# VFD_Board.net
KiCad netlist of a schematic drawn in EAGLE
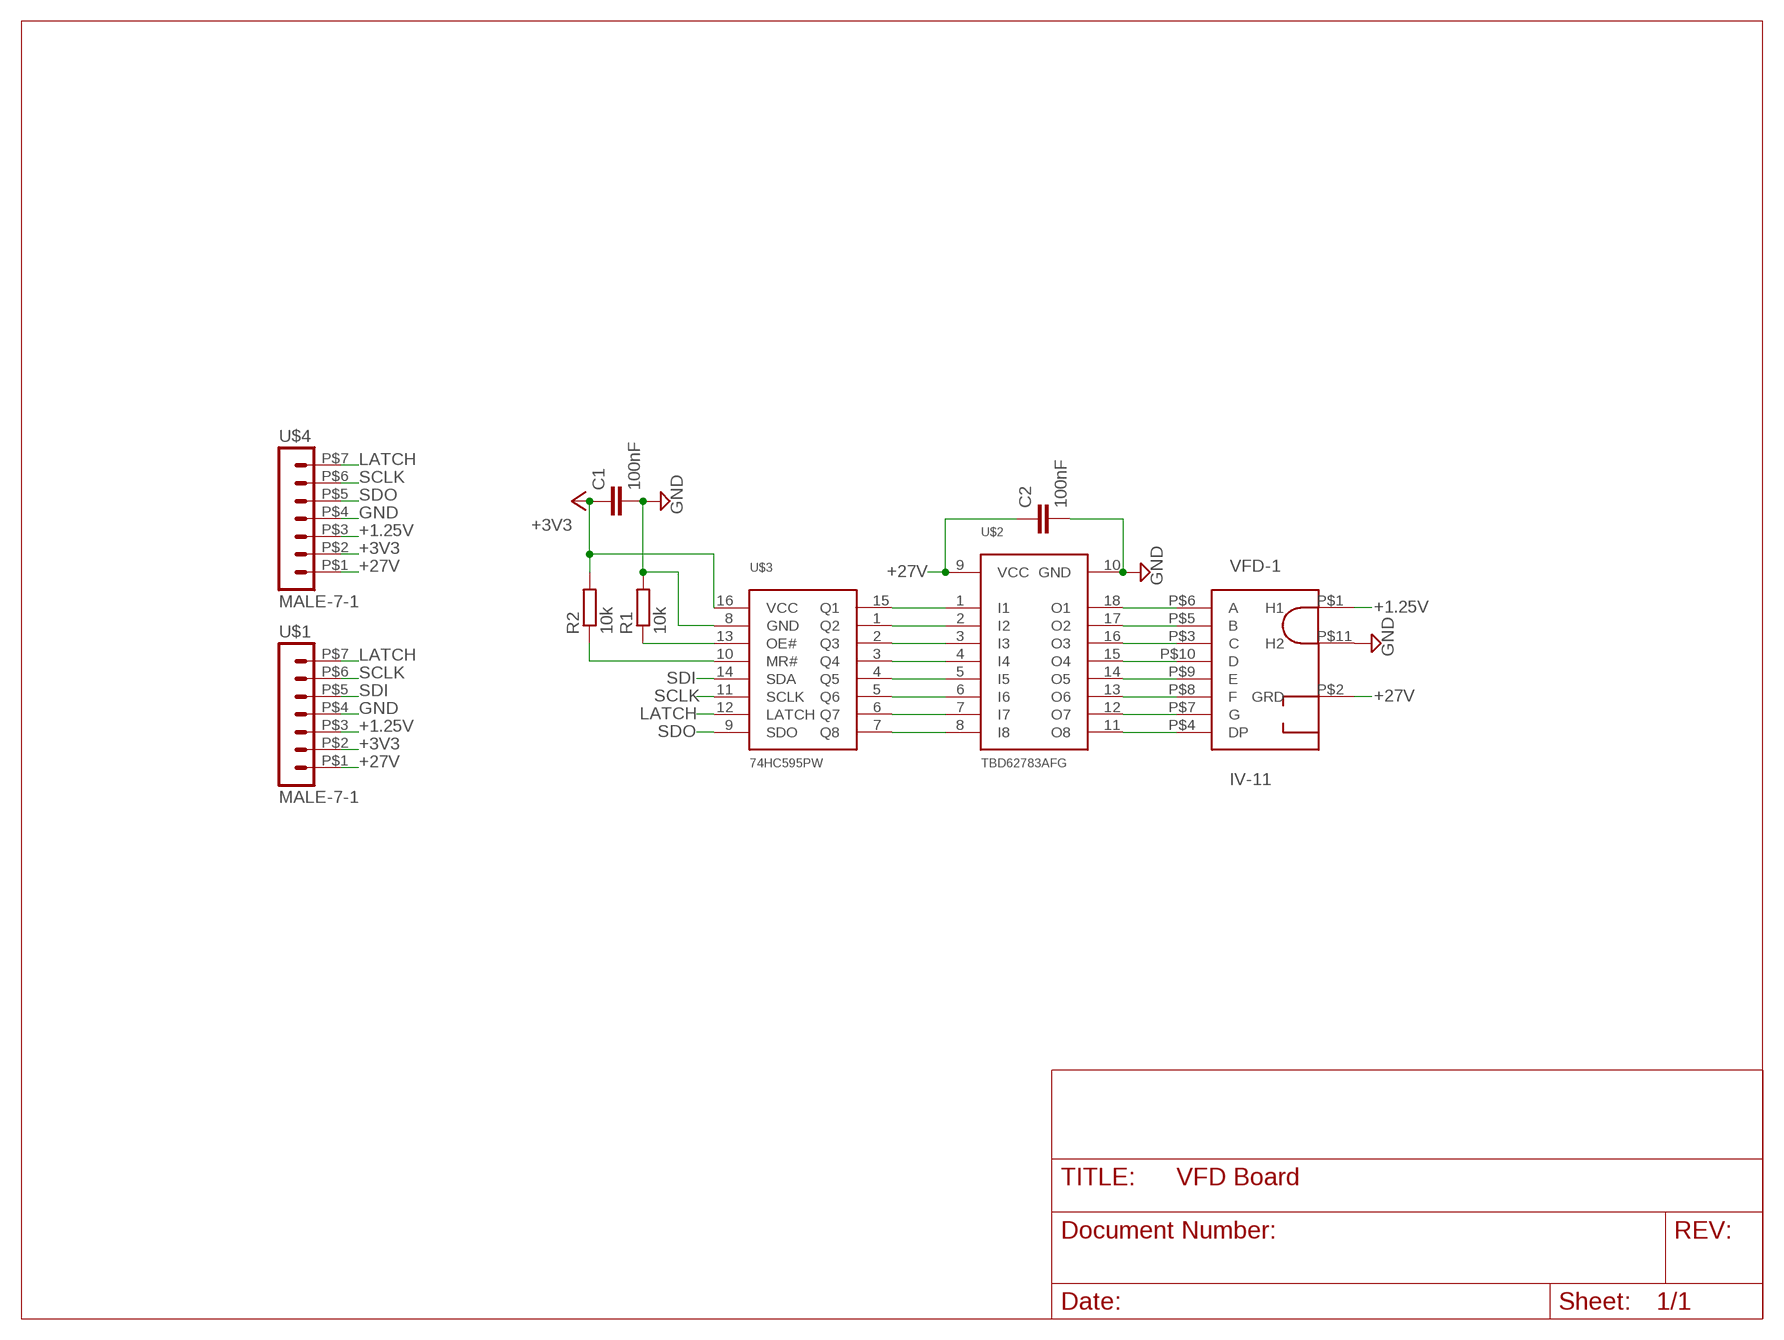
[diagram p0: schematic, sheet 1]

(export (version "E")
  (design (tool "Eeschema 10.0.6"))
  (components
    (comp (ref "C1")
      (value "100nF")
      (footprint "eagle-import:C0603")
      (libsource (lib "eagle-import") (part "C-EUC0603"))
    )
    (comp (ref "C2")
      (value "100nF")
      (footprint "eagle-import:C0603")
      (libsource (lib "eagle-import") (part "C-EUC0603"))
    )
    (comp (ref "R1")
      (value "10k")
      (footprint "eagle-import:R0603")
      (libsource (lib "eagle-import") (part "R-EU_R0603"))
    )
    (comp (ref "R2")
      (value "10k")
      (footprint "eagle-import:R0603")
      (libsource (lib "eagle-import") (part "R-EU_R0603"))
    )
    (comp (ref "U$1")
      (value "MALE-7-1")
      (footprint "eagle-import:7-PIN-HEADER")
      (libsource (lib "eagle-import") (part "MALE-7-1"))
    )
    (comp (ref "U$2")
      (value "TBD62783AFG")
      (footprint "eagle-import:SOIC18L")
      (libsource (lib "eagle-import") (part "TBD62783AFG"))
    )
    (comp (ref "U$3")
      (value "74HC595PW")
      (footprint "eagle-import:TSSOP16")
      (libsource (lib "eagle-import") (part "74HC595PW"))
    )
    (comp (ref "U$4")
      (value "MALE-7-1")
      (footprint "eagle-import:7-PIN-HEADER")
      (libsource (lib "eagle-import") (part "MALE-7-1"))
    )
    (comp (ref "VFD-1")
      (value "IV-11")
      (footprint "eagle-import:IV-11")
      (libsource (lib "eagle-import") (part "IV-11"))
    )
  )
  (nets
    (net (code "1") (name "+3V3") (class "Default")
      (node (ref "C1") (pin "1") (pinfunction "1_1") (pintype "passive"))
      (node (ref "R2") (pin "2") (pinfunction "2_2") (pintype "passive"))
      (node (ref "U$1") (pin "P$2") (pinfunction "2_P$2") (pintype "passive"))
      (node (ref "U$3") (pin "16") (pinfunction "VCC_16") (pintype "bidirectional"))
      (node (ref "U$4") (pin "P$2") (pinfunction "2_P$2") (pintype "passive"))
    )
    (net (code "2") (name "/+1.25V") (class "Default")
      (node (ref "U$1") (pin "P$3") (pinfunction "3_P$3") (pintype "passive"))
      (node (ref "U$4") (pin "P$3") (pinfunction "3_P$3") (pintype "passive"))
      (node (ref "VFD-1") (pin "P$1") (pinfunction "H1_P$1") (pintype "bidirectional"))
    )
    (net (code "3") (name "/+27V") (class "Default")
      (node (ref "C2") (pin "1") (pinfunction "1_1") (pintype "passive"))
      (node (ref "U$1") (pin "P$1") (pinfunction "1_P$1") (pintype "passive"))
      (node (ref "U$2") (pin "9") (pinfunction "VCC_9") (pintype "bidirectional"))
      (node (ref "U$4") (pin "P$1") (pinfunction "1_P$1") (pintype "passive"))
      (node (ref "VFD-1") (pin "P$2") (pinfunction "GRD_P$2") (pintype "bidirectional"))
    )
    (net (code "4") (name "/LATCH") (class "Default")
      (node (ref "U$1") (pin "P$7") (pinfunction "7_P$7") (pintype "passive"))
      (node (ref "U$3") (pin "12") (pinfunction "LATCH_12") (pintype "bidirectional"))
      (node (ref "U$4") (pin "P$7") (pinfunction "7_P$7") (pintype "passive"))
    )
    (net (code "5") (name "/SCLK") (class "Default")
      (node (ref "U$1") (pin "P$6") (pinfunction "6_P$6") (pintype "passive"))
      (node (ref "U$3") (pin "11") (pinfunction "SCLK_11") (pintype "bidirectional"))
      (node (ref "U$4") (pin "P$6") (pinfunction "6_P$6") (pintype "passive"))
    )
    (net (code "6") (name "/SDI") (class "Default")
      (node (ref "U$1") (pin "P$5") (pinfunction "5_P$5") (pintype "passive"))
      (node (ref "U$3") (pin "14") (pinfunction "SDA_14") (pintype "bidirectional"))
    )
    (net (code "7") (name "/SDO") (class "Default")
      (node (ref "U$3") (pin "9") (pinfunction "SDO_9") (pintype "bidirectional"))
      (node (ref "U$4") (pin "P$5") (pinfunction "5_P$5") (pintype "passive"))
    )
    (net (code "8") (name "GND") (class "Default")
      (node (ref "C1") (pin "2") (pinfunction "2_2") (pintype "passive"))
      (node (ref "C2") (pin "2") (pinfunction "2_2") (pintype "passive"))
      (node (ref "R1") (pin "2") (pinfunction "2_2") (pintype "passive"))
      (node (ref "U$1") (pin "P$4") (pinfunction "4_P$4") (pintype "passive"))
      (node (ref "U$2") (pin "10") (pinfunction "GND_10") (pintype "bidirectional"))
      (node (ref "U$3") (pin "8") (pinfunction "GND_8") (pintype "bidirectional"))
      (node (ref "U$4") (pin "P$4") (pinfunction "4_P$4") (pintype "passive"))
      (node (ref "VFD-1") (pin "P$11") (pinfunction "H2_P$11") (pintype "bidirectional"))
    )
    (net (code "9") (name "Net-(U$2-I1)") (class "Default")
      (node (ref "U$2") (pin "1") (pinfunction "I1_1") (pintype "bidirectional"))
      (node (ref "U$3") (pin "15") (pinfunction "Q1_15") (pintype "bidirectional"))
    )
    (net (code "10") (name "Net-(U$2-I2)") (class "Default")
      (node (ref "U$2") (pin "2") (pinfunction "I2_2") (pintype "bidirectional"))
      (node (ref "U$3") (pin "1") (pinfunction "Q2_1") (pintype "bidirectional"))
    )
    (net (code "11") (name "Net-(U$2-I3)") (class "Default")
      (node (ref "U$2") (pin "3") (pinfunction "I3_3") (pintype "bidirectional"))
      (node (ref "U$3") (pin "2") (pinfunction "Q3_2") (pintype "bidirectional"))
    )
    (net (code "12") (name "Net-(U$2-I4)") (class "Default")
      (node (ref "U$2") (pin "4") (pinfunction "I4_4") (pintype "bidirectional"))
      (node (ref "U$3") (pin "3") (pinfunction "Q4_3") (pintype "bidirectional"))
    )
    (net (code "13") (name "Net-(U$2-I5)") (class "Default")
      (node (ref "U$2") (pin "5") (pinfunction "I5_5") (pintype "bidirectional"))
      (node (ref "U$3") (pin "4") (pinfunction "Q5_4") (pintype "bidirectional"))
    )
    (net (code "14") (name "Net-(U$2-I6)") (class "Default")
      (node (ref "U$2") (pin "6") (pinfunction "I6_6") (pintype "bidirectional"))
      (node (ref "U$3") (pin "5") (pinfunction "Q6_5") (pintype "bidirectional"))
    )
    (net (code "15") (name "Net-(U$2-I7)") (class "Default")
      (node (ref "U$2") (pin "7") (pinfunction "I7_7") (pintype "bidirectional"))
      (node (ref "U$3") (pin "6") (pinfunction "Q7_6") (pintype "bidirectional"))
    )
    (net (code "16") (name "Net-(U$2-I8)") (class "Default")
      (node (ref "U$2") (pin "8") (pinfunction "I8_8") (pintype "bidirectional"))
      (node (ref "U$3") (pin "7") (pinfunction "Q8_7") (pintype "bidirectional"))
    )
    (net (code "17") (name "Net-(U$2-O1)") (class "Default")
      (node (ref "U$2") (pin "18") (pinfunction "O1_18") (pintype "bidirectional"))
      (node (ref "VFD-1") (pin "P$6") (pinfunction "A_P$6") (pintype "bidirectional"))
    )
    (net (code "18") (name "Net-(U$2-O2)") (class "Default")
      (node (ref "U$2") (pin "17") (pinfunction "O2_17") (pintype "bidirectional"))
      (node (ref "VFD-1") (pin "P$5") (pinfunction "B_P$5") (pintype "bidirectional"))
    )
    (net (code "19") (name "Net-(U$2-O3)") (class "Default")
      (node (ref "U$2") (pin "16") (pinfunction "O3_16") (pintype "bidirectional"))
      (node (ref "VFD-1") (pin "P$3") (pinfunction "C_P$3") (pintype "bidirectional"))
    )
    (net (code "20") (name "Net-(U$2-O4)") (class "Default")
      (node (ref "U$2") (pin "15") (pinfunction "O4_15") (pintype "bidirectional"))
      (node (ref "VFD-1") (pin "P$10") (pinfunction "D_P$10") (pintype "bidirectional"))
    )
    (net (code "21") (name "Net-(U$2-O5)") (class "Default")
      (node (ref "U$2") (pin "14") (pinfunction "O5_14") (pintype "bidirectional"))
      (node (ref "VFD-1") (pin "P$9") (pinfunction "E_P$9") (pintype "bidirectional"))
    )
    (net (code "22") (name "Net-(U$2-O6)") (class "Default")
      (node (ref "U$2") (pin "13") (pinfunction "O6_13") (pintype "bidirectional"))
      (node (ref "VFD-1") (pin "P$8") (pinfunction "F_P$8") (pintype "bidirectional"))
    )
    (net (code "23") (name "Net-(U$2-O7)") (class "Default")
      (node (ref "U$2") (pin "12") (pinfunction "O7_12") (pintype "bidirectional"))
      (node (ref "VFD-1") (pin "P$7") (pinfunction "G_P$7") (pintype "bidirectional"))
    )
    (net (code "24") (name "Net-(U$2-O8)") (class "Default")
      (node (ref "U$2") (pin "11") (pinfunction "O8_11") (pintype "bidirectional"))
      (node (ref "VFD-1") (pin "P$4") (pinfunction "DP_P$4") (pintype "bidirectional"))
    )
    (net (code "25") (name "Net-(U$3-MR#)") (class "Default")
      (node (ref "R2") (pin "1") (pinfunction "1_1") (pintype "passive"))
      (node (ref "U$3") (pin "10") (pinfunction "MR#_10") (pintype "bidirectional"))
    )
    (net (code "26") (name "Net-(U$3-OE#)") (class "Default")
      (node (ref "R1") (pin "1") (pinfunction "1_1") (pintype "passive"))
      (node (ref "U$3") (pin "13") (pinfunction "OE#_13") (pintype "bidirectional"))
    )
  )
)
